# OTEStamper.net
KiCad netlist of a schematic drawn in EAGLE
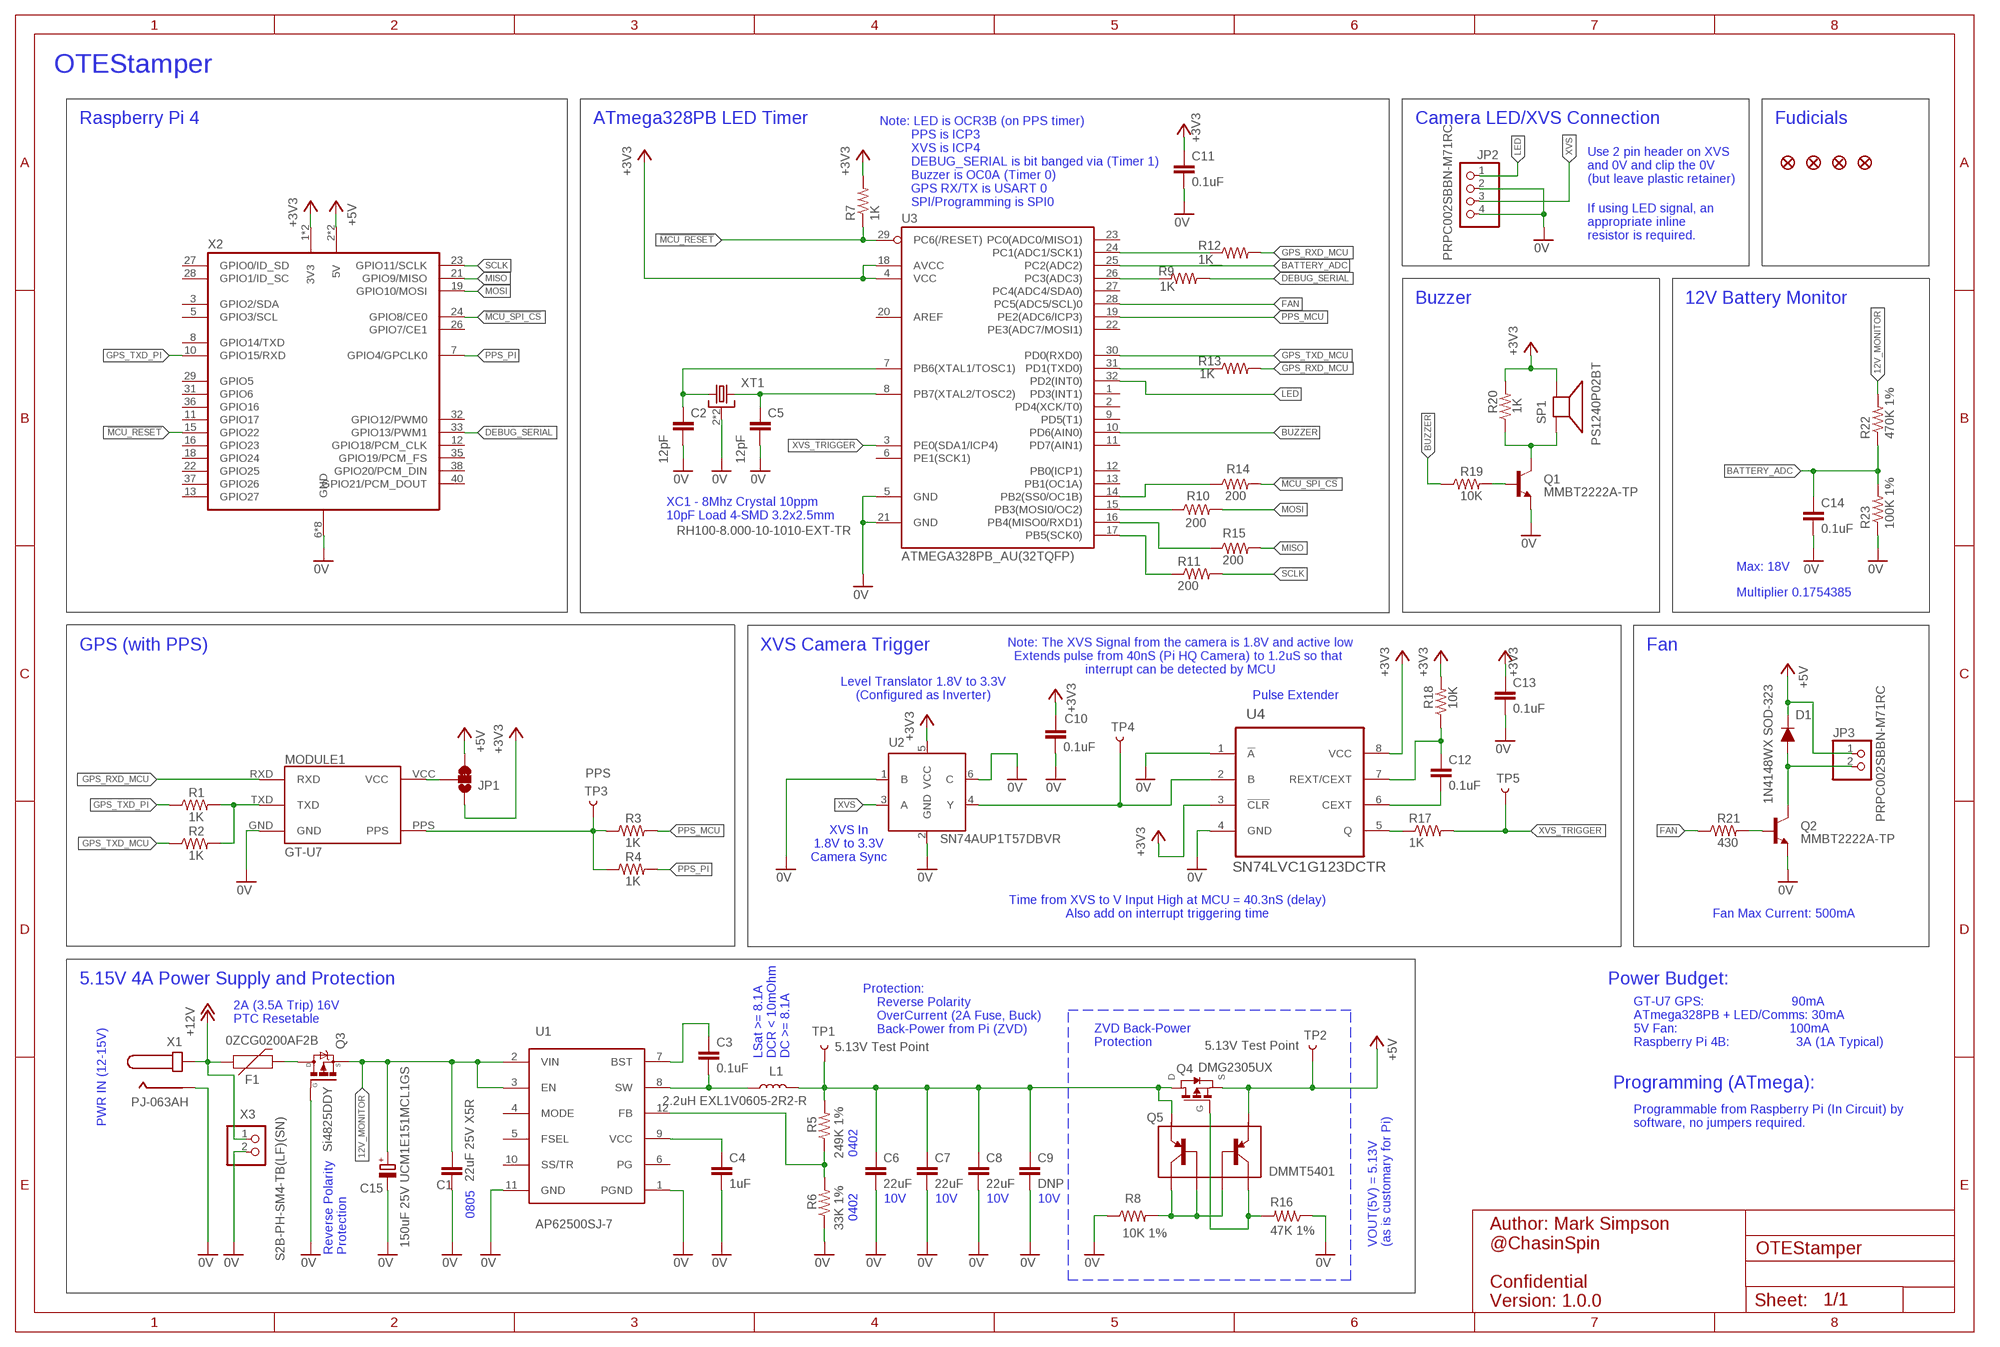
[diagram p0: schematic, sheet 1]

(export (version "E")
  (design (tool "Eeschema 10.0.6"))
  (components
    (comp (ref "C1")
      (value "22uF 25V X5R")
      (footprint "eagle-import:C0805K")
      (libsource (lib "eagle-import") (part "C-EUC0805K"))
    )
    (comp (ref "C2")
      (value "12pF")
      (footprint "eagle-import:C0603K")
      (libsource (lib "eagle-import") (part "C-EU"))
    )
    (comp (ref "C3")
      (value "0.1uF")
      (footprint "eagle-import:C0402K")
      (libsource (lib "eagle-import") (part "C-EUC0402K"))
    )
    (comp (ref "C4")
      (value "1uF")
      (footprint "eagle-import:C0402K")
      (libsource (lib "eagle-import") (part "C-EUC0402K"))
    )
    (comp (ref "C5")
      (value "12pF")
      (footprint "eagle-import:C0603K")
      (libsource (lib "eagle-import") (part "C-EU"))
    )
    (comp (ref "C6")
      (value "22uF")
      (footprint "eagle-import:C0603K")
      (libsource (lib "eagle-import") (part "C-EU"))
    )
    (comp (ref "C7")
      (value "22uF")
      (footprint "eagle-import:C0603K")
      (libsource (lib "eagle-import") (part "C-EU"))
    )
    (comp (ref "C8")
      (value "22uF")
      (footprint "eagle-import:C0603K")
      (libsource (lib "eagle-import") (part "C-EU"))
    )
    (comp (ref "C9")
      (value "DNP")
      (footprint "eagle-import:C0603K")
      (libsource (lib "eagle-import") (part "C-EU"))
    )
    (comp (ref "C10")
      (value "0.1uF")
      (footprint "eagle-import:C0603K")
      (libsource (lib "eagle-import") (part "C-EU"))
    )
    (comp (ref "C11")
      (value "0.1uF")
      (footprint "eagle-import:C0603K")
      (libsource (lib "eagle-import") (part "C-EU"))
    )
    (comp (ref "C12")
      (value "0.1uF")
      (footprint "eagle-import:C0603K")
      (libsource (lib "eagle-import") (part "C-EU"))
    )
    (comp (ref "C13")
      (value "0.1uF")
      (footprint "eagle-import:C0603K")
      (libsource (lib "eagle-import") (part "C-EU"))
    )
    (comp (ref "C14")
      (value "0.1uF")
      (footprint "eagle-import:C0603K")
      (libsource (lib "eagle-import") (part "C-EU"))
    )
    (comp (ref "C15")
      (value "150uF 25V UCM1E151MCL1GS")
      (footprint "eagle-import:UD-6,3X7,7_NICHICON")
      (libsource (lib "eagle-import") (part "CPOL-EUUD-6,3X7,7"))
    )
    (comp (ref "D1")
      (value "1N4148WX SOD-323")
      (footprint "eagle-import:SOD-323")
      (libsource (lib "eagle-import") (part "DIODE"))
    )
    (comp (ref "F1")
      (value "0ZCG0200AF2B")
      (footprint "eagle-import:F1812")
      (libsource (lib "eagle-import") (part "FUSE-PTCF1812"))
    )
    (comp (ref "FD1")
      (value "FIDUCIALUFIDUCIAL")
      (footprint "eagle-import:FIDUCIAL-MICRO")
      (libsource (lib "eagle-import") (part "FIDUCIALUFIDUCIAL"))
    )
    (comp (ref "FD2")
      (value "FIDUCIALUFIDUCIAL")
      (footprint "eagle-import:FIDUCIAL-MICRO")
      (libsource (lib "eagle-import") (part "FIDUCIALUFIDUCIAL"))
    )
    (comp (ref "FD3")
      (value "FIDUCIALUFIDUCIAL")
      (footprint "eagle-import:FIDUCIAL-MICRO")
      (libsource (lib "eagle-import") (part "FIDUCIALUFIDUCIAL"))
    )
    (comp (ref "FD4")
      (value "FIDUCIALUFIDUCIAL")
      (footprint "eagle-import:FIDUCIAL-MICRO")
      (libsource (lib "eagle-import") (part "FIDUCIALUFIDUCIAL"))
    )
    (comp (ref "JP1")
      (value "JUMPER-SMT_3_1-NC_TRACE_SILK")
      (footprint "eagle-import:SMT-JUMPER_3_1-NC_TRACE_SILK")
      (libsource (lib "eagle-import") (part "JUMPER-SMT_3_1-NC_TRACE_SILK"))
    )
    (comp (ref "JP2")
      (value "PRPC002SBBN-M71RC")
      (footprint "eagle-import:1X04")
      (libsource (lib "eagle-import") (part "PINHD-1X4"))
    )
    (comp (ref "JP3")
      (value "PRPC002SBBN-M71RC")
      (footprint "eagle-import:1X02")
      (libsource (lib "eagle-import") (part "PINHD-1X2"))
    )
    (comp (ref "L1")
      (value "2.2uH EXL1V0605-2R2-R")
      (footprint "eagle-import:EXL1V0605")
      (libsource (lib "eagle-import") (part "EXL1V0605"))
    )
    (comp (ref "MODULE1")
      (value "GT-U7")
      (footprint "eagle-import:GT-U7")
      (libsource (lib "eagle-import") (part "GT-U7"))
    )
    (comp (ref "Q1")
      (value "MMBT2222A-TP")
      (footprint "eagle-import:SOT23-BEC")
      (libsource (lib "eagle-import") (part "MMBT3904LT1G"))
    )
    (comp (ref "Q2")
      (value "MMBT2222A-TP")
      (footprint "eagle-import:SOT23-BEC")
      (libsource (lib "eagle-import") (part "MMBT3904LT1G"))
    )
    (comp (ref "Q3")
      (value "Si4825DDY")
      (footprint "eagle-import:SOIC-8-BAR")
      (libsource (lib "eagle-import") (part "SI4825DDY"))
    )
    (comp (ref "Q4")
      (value "DMG2305UX")
      (footprint "eagle-import:SI2323DDS")
      (libsource (lib "eagle-import") (part "SI2323DDS"))
    )
    (comp (ref "Q5")
      (value "DMMT5401")
      (footprint "eagle-import:SOT26(SC74R)")
      (libsource (lib "eagle-import") (part "DMMT5401"))
    )
    (comp (ref "R1")
      (value "1K")
      (footprint "eagle-import:R0603")
      (libsource (lib "eagle-import") (part "R-US"))
    )
    (comp (ref "R2")
      (value "1K")
      (footprint "eagle-import:R0603")
      (libsource (lib "eagle-import") (part "R-US"))
    )
    (comp (ref "R3")
      (value "1K")
      (footprint "eagle-import:R0603")
      (libsource (lib "eagle-import") (part "R-US"))
    )
    (comp (ref "R4")
      (value "1K")
      (footprint "eagle-import:R0603")
      (libsource (lib "eagle-import") (part "R-US"))
    )
    (comp (ref "R5")
      (value "249K 1%")
      (footprint "eagle-import:R0402")
      (libsource (lib "eagle-import") (part "R-USR0402"))
    )
    (comp (ref "R6")
      (value "33K 1%")
      (footprint "eagle-import:R0402")
      (libsource (lib "eagle-import") (part "R-USR0402"))
    )
    (comp (ref "R7")
      (value "1K")
      (footprint "eagle-import:R0603")
      (libsource (lib "eagle-import") (part "R-US"))
    )
    (comp (ref "R8")
      (value "10K 1%")
      (footprint "eagle-import:R0603")
      (libsource (lib "eagle-import") (part "R-US"))
    )
    (comp (ref "R9")
      (value "1K")
      (footprint "eagle-import:R0603")
      (libsource (lib "eagle-import") (part "R-US"))
    )
    (comp (ref "R10")
      (value "200")
      (footprint "eagle-import:R0603")
      (libsource (lib "eagle-import") (part "R-US"))
    )
    (comp (ref "R11")
      (value "200")
      (footprint "eagle-import:R0603")
      (libsource (lib "eagle-import") (part "R-US"))
    )
    (comp (ref "R12")
      (value "1K")
      (footprint "eagle-import:R0603")
      (libsource (lib "eagle-import") (part "R-US"))
    )
    (comp (ref "R13")
      (value "1K")
      (footprint "eagle-import:R0603")
      (libsource (lib "eagle-import") (part "R-US"))
    )
    (comp (ref "R14")
      (value "200")
      (footprint "eagle-import:R0603")
      (libsource (lib "eagle-import") (part "R-US"))
    )
    (comp (ref "R15")
      (value "200")
      (footprint "eagle-import:R0603")
      (libsource (lib "eagle-import") (part "R-US"))
    )
    (comp (ref "R16")
      (value "47K 1%")
      (footprint "eagle-import:R0603")
      (libsource (lib "eagle-import") (part "R-US"))
    )
    (comp (ref "R17")
      (value "1K")
      (footprint "eagle-import:R0603")
      (libsource (lib "eagle-import") (part "R-US"))
    )
    (comp (ref "R18")
      (value "10K")
      (footprint "eagle-import:R0603")
      (libsource (lib "eagle-import") (part "R-US"))
    )
    (comp (ref "R19")
      (value "10K")
      (footprint "eagle-import:R0603")
      (libsource (lib "eagle-import") (part "R-US"))
    )
    (comp (ref "R20")
      (value "1K")
      (footprint "eagle-import:R0603")
      (libsource (lib "eagle-import") (part "R-US"))
    )
    (comp (ref "R21")
      (value "430")
      (footprint "eagle-import:R0603")
      (libsource (lib "eagle-import") (part "R-US"))
    )
    (comp (ref "R22")
      (value "470K 1%")
      (footprint "eagle-import:R0603")
      (libsource (lib "eagle-import") (part "R-US"))
    )
    (comp (ref "R23")
      (value "100K 1%")
      (footprint "eagle-import:R0603")
      (libsource (lib "eagle-import") (part "R-US"))
    )
    (comp (ref "SP1")
      (value "PS1240P02BT")
      (footprint "eagle-import:PS12")
      (libsource (lib "eagle-import") (part "PS12/PS12"))
    )
    (comp (ref "TP1")
      (value "5.13V Test Point")
      (footprint "eagle-import:PAD.03X.03")
      (libsource (lib "eagle-import") (part "TEST-POINT3"))
    )
    (comp (ref "TP2")
      (value "5.13V Test Point")
      (footprint "eagle-import:PAD.03X.03")
      (libsource (lib "eagle-import") (part "TEST-POINT3"))
    )
    (comp (ref "TP3")
      (value "PPS")
      (footprint "eagle-import:PAD.03X.03")
      (libsource (lib "eagle-import") (part "TEST-POINT3"))
    )
    (comp (ref "TP4")
      (value "TEST-POINT3")
      (footprint "eagle-import:PAD.03X.03")
      (libsource (lib "eagle-import") (part "TEST-POINT3"))
    )
    (comp (ref "TP5")
      (value "TEST-POINT3")
      (footprint "eagle-import:PAD.03X.03")
      (libsource (lib "eagle-import") (part "TEST-POINT3"))
    )
    (comp (ref "U1")
      (value "AP62500SJ-7")
      (footprint "eagle-import:AP62500")
      (libsource (lib "eagle-import") (part "AP62500"))
    )
    (comp (ref "U2")
      (value "SN74AUP1T57DBVR")
      (footprint "eagle-import:SOT23-6-DBV")
      (libsource (lib "eagle-import") (part "SN74AUP1T57"))
    )
    (comp (ref "U3")
      (value "ATMEGA328PB_AU(32TQFP)")
      (footprint "eagle-import:TQFP32-08")
      (libsource (lib "eagle-import") (part "ATMEGA328PB_TQFP"))
    )
    (comp (ref "U4")
      (value "SN74LVC1G123DCTR")
      (footprint "eagle-import:SSOP-8-DCT")
      (libsource (lib "eagle-import") (part "SN74LVC1G123DCT"))
    )
    (comp (ref "X1")
      (value "PJ-063AH")
      (footprint "eagle-import:PJ-063AH")
      (libsource (lib "eagle-import") (part "PJ-063AH"))
    )
    (comp (ref "X2")
      (value "ADAFRUIT_2222")
      (footprint "eagle-import:RASPBERRY_PI_HAT")
      (libsource (lib "eagle-import") (part "RASPBERRY_PI_HAT"))
    )
    (comp (ref "X3")
      (value "S2B-PH-SM4-TB(LF)(SN)")
      (footprint "eagle-import:JST-PH-2-SMT-RA")
      (libsource (lib "eagle-import") (part "S2B-PH-SM4-TB(LF)(SN)"))
    )
    (comp (ref "XT1")
      (value "RH100-8.000-10-1010-EXT-TR")
      (footprint "eagle-import:ECS-ECX-32")
      (libsource (lib "eagle-import") (part "ECS-ECX-32"))
    )
  )
  (nets
    (net (code "1") (name "+3V3") (class "Default")
      (node (ref "C10") (pin "1") (pinfunction "1_1") (pintype "passive"))
      (node (ref "C11") (pin "1") (pinfunction "1_1") (pintype "passive"))
      (node (ref "C13") (pin "1") (pinfunction "1_1") (pintype "passive"))
      (node (ref "JP1") (pin "1") (pinfunction "1_1") (pintype "passive"))
      (node (ref "R18") (pin "2") (pinfunction "2_2") (pintype "passive"))
      (node (ref "R20") (pin "2") (pinfunction "2_2") (pintype "passive"))
      (node (ref "R7") (pin "2") (pinfunction "2_2") (pintype "passive"))
      (node (ref "SP1") (pin "P$1") (pinfunction "+_P$1") (pintype "passive"))
      (node (ref "U2") (pin "5") (pinfunction "VCC_5") (pintype "power_in"))
      (node (ref "U3") (pin "18") (pinfunction "AVCC_18") (pintype "bidirectional"))
      (node (ref "U3") (pin "4") (pinfunction "VCC_4") (pintype "bidirectional"))
      (node (ref "U4") (pin "3") (pinfunction "~{CLR}_3") (pintype "input"))
      (node (ref "U4") (pin "8") (pinfunction "VCC_8") (pintype "power_in"))
      (node (ref "X2") (pin "1") (pinfunction "3V3_1") (pintype "bidirectional"))
      (node (ref "X2") (pin "17") (pinfunction "3V3_17") (pintype "bidirectional"))
    )
    (net (code "2") (name "+5V") (class "Default")
      (node (ref "D1") (pin "CATHODE") (pinfunction "K_CATHODE") (pintype "passive"))
      (node (ref "JP1") (pin "3") (pinfunction "3_3") (pintype "passive"))
      (node (ref "JP3") (pin "1") (pinfunction "1_1") (pintype "passive"))
      (node (ref "Q4") (pin "2") (pinfunction "S_2") (pintype "passive"))
      (node (ref "Q5") (pin "5") (pinfunction "E2_5") (pintype "passive"))
      (node (ref "TP2") (pin "P$1") (pinfunction "1_P$1") (pintype "bidirectional"))
      (node (ref "X2") (pin "2") (pinfunction "5V_2") (pintype "bidirectional"))
      (node (ref "X2") (pin "4") (pinfunction "5V_4") (pintype "bidirectional"))
    )
    (net (code "3") (name "+12V") (class "Default")
      (node (ref "F1") (pin "1") (pinfunction "1_1") (pintype "bidirectional"))
      (node (ref "X1") (pin "1") (pinfunction "POS_1") (pintype "passive"))
      (node (ref "X3") (pin "1") (pinfunction "1_1") (pintype "passive"))
    )
    (net (code "4") (name "/~{MCU_RESET}") (class "Default")
      (node (ref "R7") (pin "1") (pinfunction "1_1") (pintype "passive"))
      (node (ref "U3") (pin "29") (pinfunction "PC6(/RESET)_29") (pintype "bidirectional"))
      (node (ref "X2") (pin "15") (pinfunction "GPIO22_15") (pintype "bidirectional"))
    )
    (net (code "5") (name "/~{MCU_SPI_CS}") (class "Default")
      (node (ref "R14") (pin "2") (pinfunction "2_2") (pintype "passive"))
      (node (ref "X2") (pin "24") (pinfunction "GPIO8/CE0_24") (pintype "bidirectional"))
    )
    (net (code "6") (name "0V") (class "Default")
      (node (ref "C1") (pin "2") (pinfunction "2_2") (pintype "passive"))
      (node (ref "C10") (pin "2") (pinfunction "2_2") (pintype "passive"))
      (node (ref "C11") (pin "2") (pinfunction "2_2") (pintype "passive"))
      (node (ref "C13") (pin "2") (pinfunction "2_2") (pintype "passive"))
      (node (ref "C14") (pin "2") (pinfunction "2_2") (pintype "passive"))
      (node (ref "C15") (pin "-") (pinfunction "-_-") (pintype "passive"))
      (node (ref "C2") (pin "2") (pinfunction "2_2") (pintype "passive"))
      (node (ref "C4") (pin "2") (pinfunction "2_2") (pintype "passive"))
      (node (ref "C5") (pin "2") (pinfunction "2_2") (pintype "passive"))
      (node (ref "C6") (pin "2") (pinfunction "2_2") (pintype "passive"))
      (node (ref "C7") (pin "2") (pinfunction "2_2") (pintype "passive"))
      (node (ref "C8") (pin "2") (pinfunction "2_2") (pintype "passive"))
      (node (ref "C9") (pin "2") (pinfunction "2_2") (pintype "passive"))
      (node (ref "JP2") (pin "2") (pinfunction "2_2") (pintype "passive"))
      (node (ref "JP2") (pin "4") (pinfunction "4_4") (pintype "passive"))
      (node (ref "MODULE1") (pin "GND") (pinfunction "GND_GND") (pintype "power_in"))
      (node (ref "Q1") (pin "E") (pinfunction "E_E") (pintype "passive"))
      (node (ref "Q2") (pin "E") (pinfunction "E_E") (pintype "passive"))
      (node (ref "Q3") (pin "4") (pinfunction "G_4") (pintype "passive"))
      (node (ref "R16") (pin "1") (pinfunction "1_1") (pintype "passive"))
      (node (ref "R23") (pin "1") (pinfunction "1_1") (pintype "passive"))
      (node (ref "R6") (pin "1") (pinfunction "1_1") (pintype "passive"))
      (node (ref "R8") (pin "1") (pinfunction "1_1") (pintype "passive"))
      (node (ref "U1") (pin "1") (pinfunction "PGND_1") (pintype "power_in"))
      (node (ref "U1") (pin "11") (pinfunction "GND_11") (pintype "power_in"))
      (node (ref "U2") (pin "1") (pinfunction "B_1") (pintype "input"))
      (node (ref "U2") (pin "2") (pinfunction "GND_2") (pintype "power_in"))
      (node (ref "U2") (pin "6") (pinfunction "C_6") (pintype "input"))
      (node (ref "U3") (pin "21") (pinfunction "GND_21") (pintype "bidirectional"))
      (node (ref "U3") (pin "5") (pinfunction "GND_5") (pintype "bidirectional"))
      (node (ref "U4") (pin "1") (pinfunction "~{A}_1") (pintype "input"))
      (node (ref "U4") (pin "4") (pinfunction "GND_4") (pintype "power_in"))
      (node (ref "X1") (pin "2") (pinfunction "NEG_2") (pintype "passive"))
      (node (ref "X1") (pin "SHIELD1") (pinfunction "NEG_SHIELD1") (pintype "passive"))
      (node (ref "X1") (pin "SHIELD2") (pinfunction "NEG_SHIELD2") (pintype "passive"))
      (node (ref "X2") (pin "14") (pinfunction "GND_14") (pintype "bidirectional"))
      (node (ref "X2") (pin "20") (pinfunction "GND_20") (pintype "bidirectional"))
      (node (ref "X2") (pin "25") (pinfunction "GND_25") (pintype "bidirectional"))
      (node (ref "X2") (pin "30") (pinfunction "GND_30") (pintype "bidirectional"))
      (node (ref "X2") (pin "34") (pinfunction "GND_34") (pintype "bidirectional"))
      (node (ref "X2") (pin "39") (pinfunction "GND_39") (pintype "bidirectional"))
      (node (ref "X2") (pin "6") (pinfunction "GND_6") (pintype "bidirectional"))
      (node (ref "X2") (pin "9") (pinfunction "GND_9") (pintype "bidirectional"))
      (node (ref "X3") (pin "2") (pinfunction "2_2") (pintype "passive"))
      (node (ref "XT1") (pin "2") (pinfunction "3_2") (pintype "power_in"))
      (node (ref "XT1") (pin "4") (pinfunction "3_4") (pintype "power_in"))
    )
    (net (code "7") (name "12V_MONITOR") (class "Default")
      (node (ref "C1") (pin "1") (pinfunction "1_1") (pintype "passive"))
      (node (ref "C15") (pin "+") (pinfunction "+_+") (pintype "passive"))
      (node (ref "Q3") (pin "1") (pinfunction "S_1") (pintype "passive"))
      (node (ref "Q3") (pin "2") (pinfunction "S_2") (pintype "passive"))
      (node (ref "Q3") (pin "3") (pinfunction "S_3") (pintype "passive"))
      (node (ref "R22") (pin "2") (pinfunction "2_2") (pintype "passive"))
      (node (ref "U1") (pin "2") (pinfunction "VIN_2") (pintype "power_in"))
      (node (ref "U1") (pin "3") (pinfunction "EN_3") (pintype "input"))
    )
    (net (code "8") (name "BATTERY_ADC") (class "Default")
      (node (ref "C14") (pin "1") (pinfunction "1_1") (pintype "passive"))
      (node (ref "R22") (pin "1") (pinfunction "1_1") (pintype "passive"))
      (node (ref "R23") (pin "2") (pinfunction "2_2") (pintype "passive"))
      (node (ref "U3") (pin "25") (pinfunction "PC2(ADC2)_25") (pintype "bidirectional"))
    )
    (net (code "9") (name "BUZZER") (class "Default")
      (node (ref "R19") (pin "1") (pinfunction "1_1") (pintype "passive"))
      (node (ref "U3") (pin "10") (pinfunction "PD6(AIN0)_10") (pintype "bidirectional"))
    )
    (net (code "10") (name "DEBUG_SERIAL") (class "Default")
      (node (ref "R9") (pin "2") (pinfunction "2_2") (pintype "passive"))
      (node (ref "X2") (pin "33") (pinfunction "GPIO13/PWM1_33") (pintype "bidirectional"))
    )
    (net (code "11") (name "FAN") (class "Default")
      (node (ref "R21") (pin "1") (pinfunction "1_1") (pintype "passive"))
      (node (ref "U3") (pin "28") (pinfunction "PC5(ADC5/SCL)0_28") (pintype "bidirectional"))
    )
    (net (code "12") (name "GPS_RXD_MCU") (class "Default")
      (node (ref "MODULE1") (pin "RXD") (pinfunction "RXD_RXD") (pintype "input"))
      (node (ref "R12") (pin "2") (pinfunction "2_2") (pintype "passive"))
      (node (ref "R13") (pin "2") (pinfunction "2_2") (pintype "passive"))
    )
    (net (code "13") (name "GPS_TXD_MCU") (class "Default")
      (node (ref "R2") (pin "1") (pinfunction "1_1") (pintype "passive"))
      (node (ref "U3") (pin "30") (pinfunction "PD0(RXD0)_30") (pintype "bidirectional"))
    )
    (net (code "14") (name "GPS_TXD_PI") (class "Default")
      (node (ref "R1") (pin "1") (pinfunction "1_1") (pintype "passive"))
      (node (ref "X2") (pin "10") (pinfunction "GPIO15/RXD_10") (pintype "bidirectional"))
    )
    (net (code "15") (name "LED") (class "Default")
      (node (ref "JP2") (pin "1") (pinfunction "1_1") (pintype "passive"))
      (node (ref "U3") (pin "32") (pinfunction "PD2(INT0)_32") (pintype "bidirectional"))
    )
    (net (code "16") (name "MISO") (class "Default")
      (node (ref "R15") (pin "2") (pinfunction "2_2") (pintype "passive"))
      (node (ref "X2") (pin "21") (pinfunction "GPIO9/MISO_21") (pintype "bidirectional"))
    )
    (net (code "17") (name "MOSI") (class "Default")
      (node (ref "R10") (pin "2") (pinfunction "2_2") (pintype "passive"))
      (node (ref "X2") (pin "19") (pinfunction "GPIO10/MOSI_19") (pintype "bidirectional"))
    )
    (net (code "18") (name "Net-(D1-A)") (class "Default")
      (node (ref "D1") (pin "ANODE") (pinfunction "A_ANODE") (pintype "passive"))
      (node (ref "JP3") (pin "2") (pinfunction "2_2") (pintype "passive"))
      (node (ref "Q2") (pin "C") (pinfunction "C_C") (pintype "passive"))
    )
    (net (code "19") (name "Net-(F1-Pad2)") (class "Default")
      (node (ref "F1") (pin "2") (pinfunction "2_2") (pintype "bidirectional"))
      (node (ref "Q3") (pin "5") (pinfunction "D_5") (pintype "passive"))
      (node (ref "Q3") (pin "6") (pinfunction "D_6") (pintype "passive"))
      (node (ref "Q3") (pin "7") (pinfunction "D_7") (pintype "passive"))
      (node (ref "Q3") (pin "8") (pinfunction "D_8") (pintype "passive"))
    )
    (net (code "20") (name "Net-(JP1-Pad2)") (class "Default")
      (node (ref "JP1") (pin "2") (pinfunction "2_2") (pintype "passive"))
      (node (ref "MODULE1") (pin "VCC") (pinfunction "VCC_VCC") (pintype "power_in"))
    )
    (net (code "21") (name "Net-(MODULE1-PadTXD)") (class "Default")
      (node (ref "MODULE1") (pin "TXD") (pinfunction "TXD_TXD") (pintype "output"))
      (node (ref "R1") (pin "2") (pinfunction "2_2") (pintype "passive"))
      (node (ref "R2") (pin "2") (pinfunction "2_2") (pintype "passive"))
    )
    (net (code "22") (name "Net-(Q1-PadB)") (class "Default")
      (node (ref "Q1") (pin "B") (pinfunction "B_B") (pintype "passive"))
      (node (ref "R19") (pin "2") (pinfunction "2_2") (pintype "passive"))
    )
    (net (code "23") (name "Net-(Q2-PadB)") (class "Default")
      (node (ref "Q2") (pin "B") (pinfunction "B_B") (pintype "passive"))
      (node (ref "R21") (pin "2") (pinfunction "2_2") (pintype "passive"))
    )
    (net (code "24") (name "Net-(Q4-D)") (class "Default")
      (node (ref "C6") (pin "1") (pinfunction "1_1") (pintype "passive"))
      (node (ref "C7") (pin "1") (pinfunction "1_1") (pintype "passive"))
      (node (ref "C8") (pin "1") (pinfunction "1_1") (pintype "passive"))
      (node (ref "C9") (pin "1") (pinfunction "1_1") (pintype "passive"))
      (node (ref "L1") (pin "2") (pinfunction "2_2") (pintype "passive"))
      (node (ref "Q4") (pin "3") (pinfunction "D_3") (pintype "passive"))
      (node (ref "Q5") (pin "6") (pinfunction "E1_6") (pintype "passive"))
      (node (ref "R5") (pin "2") (pinfunction "2_2") (pintype "passive"))
      (node (ref "TP1") (pin "P$1") (pinfunction "1_P$1") (pintype "bidirectional"))
    )
    (net (code "25") (name "Net-(Q4-G)") (class "Default")
      (node (ref "Q4") (pin "1") (pinfunction "G_1") (pintype "passive"))
      (node (ref "Q5") (pin "4") (pinfunction "C2_4") (pintype "passive"))
      (node (ref "R16") (pin "2") (pinfunction "2_2") (pintype "passive"))
    )
    (net (code "26") (name "Net-(Q5-B1)") (class "Default")
      (node (ref "Q5") (pin "1") (pinfunction "C1_1") (pintype "passive"))
      (node (ref "Q5") (pin "2") (pinfunction "B1_2") (pintype "passive"))
      (node (ref "Q5") (pin "3") (pinfunction "B2_3") (pintype "passive"))
      (node (ref "R8") (pin "2") (pinfunction "2_2") (pintype "passive"))
    )
    (net (code "27") (name "Net-(SP1--)") (class "Default")
      (node (ref "Q1") (pin "C") (pinfunction "C_C") (pintype "passive"))
      (node (ref "R20") (pin "1") (pinfunction "1_1") (pintype "passive"))
      (node (ref "SP1") (pin "P$2") (pinfunction "-_P$2") (pintype "passive"))
    )
    (net (code "28") (name "Net-(TP3-1)") (class "Default")
      (node (ref "MODULE1") (pin "PPS") (pinfunction "PPS_PPS") (pintype "output"))
      (node (ref "R3") (pin "1") (pinfunction "1_1") (pintype "passive"))
      (node (ref "R4") (pin "1") (pinfunction "1_1") (pintype "passive"))
      (node (ref "TP3") (pin "P$1") (pinfunction "1_P$1") (pintype "bidirectional"))
    )
    (net (code "29") (name "Net-(TP4-1)") (class "Default")
      (node (ref "TP4") (pin "P$1") (pinfunction "1_P$1") (pintype "bidirectional"))
      (node (ref "U2") (pin "4") (pinfunction "Y_4") (pintype "output"))
      (node (ref "U4") (pin "2") (pinfunction "B_2") (pintype "input"))
    )
    (net (code "30") (name "Net-(U1-BST)") (class "Default")
      (node (ref "C3") (pin "1") (pinfunction "1_1") (pintype "passive"))
      (node (ref "U1") (pin "7") (pinfunction "BST_7") (pintype "input"))
    )
    (net (code "31") (name "Net-(U1-FB)") (class "Default")
      (node (ref "R5") (pin "1") (pinfunction "1_1") (pintype "passive"))
      (node (ref "R6") (pin "2") (pinfunction "2_2") (pintype "passive"))
      (node (ref "U1") (pin "12") (pinfunction "FB_12") (pintype "input"))
    )
    (net (code "32") (name "Net-(U1-SW)") (class "Default")
      (node (ref "C3") (pin "2") (pinfunction "2_2") (pintype "passive"))
      (node (ref "L1") (pin "1") (pinfunction "1_1") (pintype "passive"))
      (node (ref "U1") (pin "8") (pinfunction "SW_8") (pintype "power_in"))
    )
    (net (code "33") (name "Net-(U1-VCC)") (class "Default")
      (node (ref "C4") (pin "1") (pinfunction "1_1") (pintype "passive"))
      (node (ref "U1") (pin "9") (pinfunction "VCC_9") (pintype "power_in"))
    )
    (net (code "34") (name "Net-(U3-PB2(SS0{slash}OC1B))") (class "Default")
      (node (ref "R14") (pin "1") (pinfunction "1_1") (pintype "passive"))
      (node (ref "U3") (pin "14") (pinfunction "PB2(SS0/OC1B)_14") (pintype "bidirectional"))
    )
    (net (code "35") (name "Net-(U3-PB3(MOSI0{slash}OC2))") (class "Default")
      (node (ref "R10") (pin "1") (pinfunction "1_1") (pintype "passive"))
      (node (ref "U3") (pin "15") (pinfunction "PB3(MOSI0/OC2)_15") (pintype "bidirectional"))
    )
    (net (code "36") (name "Net-(U3-PB4(MISO0{slash}RXD1))") (class "Default")
      (node (ref "R15") (pin "1") (pinfunction "1_1") (pintype "passive"))
      (node (ref "U3") (pin "16") (pinfunction "PB4(MISO0/RXD1)_16") (pintype "bidirectional"))
    )
    (net (code "37") (name "Net-(U3-PB5(SCK0))") (class "Default")
      (node (ref "R11") (pin "1") (pinfunction "1_1") (pintype "passive"))
      (node (ref "U3") (pin "17") (pinfunction "PB5(SCK0)_17") (pintype "bidirectional"))
    )
    (net (code "38") (name "Net-(U3-PB6(XTAL1{slash}TOSC1))") (class "Default")
      (node (ref "C2") (pin "1") (pinfunction "1_1") (pintype "passive"))
      (node (ref "U3") (pin "7") (pinfunction "PB6(XTAL1/TOSC1)_7") (pintype "bidirectional"))
      (node (ref "XT1") (pin "1") (pinfunction "1_1") (pintype "passive"))
    )
    (net (code "39") (name "Net-(U3-PB7(XTAL2{slash}TOSC2))") (class "Default")
      (node (ref "C5") (pin "1") (pinfunction "1_1") (pintype "passive"))
      (node (ref "U3") (pin "8") (pinfunction "PB7(XTAL2/TOSC2)_8") (pintype "bidirectional"))
      (node (ref "XT1") (pin "3") (pinfunction "2_3") (pintype "passive"))
    )
    (net (code "40") (name "Net-(U3-PC1(ADC1{slash}SCK1))") (class "Default")
      (node (ref "R12") (pin "1") (pinfunction "1_1") (pintype "passive"))
      (node (ref "U3") (pin "24") (pinfunction "PC1(ADC1/SCK1)_24") (pintype "bidirectional"))
    )
    (net (code "41") (name "Net-(U3-PC3(ADC3))") (class "Default")
      (node (ref "R9") (pin "1") (pinfunction "1_1") (pintype "passive"))
      (node (ref "U3") (pin "26") (pinfunction "PC3(ADC3)_26") (pintype "bidirectional"))
    )
    (net (code "42") (name "Net-(U3-PD1(TXD0))") (class "Default")
      (node (ref "R13") (pin "1") (pinfunction "1_1") (pintype "passive"))
      (node (ref "U3") (pin "31") (pinfunction "PD1(TXD0)_31") (pintype "bidirectional"))
    )
    (net (code "43") (name "Net-(U4-CEXT)") (class "Default")
      (node (ref "C12") (pin "2") (pinfunction "2_2") (pintype "passive"))
      (node (ref "U4") (pin "6") (pinfunction "CEXT_6") (pintype "passive"))
    )
    (net (code "44") (name "Net-(U4-Q)") (class "Default")
      (node (ref "R17") (pin "1") (pinfunction "1_1") (pintype "passive"))
      (node (ref "U4") (pin "5") (pinfunction "Q_5") (pintype "output"))
    )
    (net (code "45") (name "Net-(U4-REXT{slash}CEXT)") (class "Default")
      (node (ref "C12") (pin "1") (pinfunction "1_1") (pintype "passive"))
      (node (ref "R18") (pin "1") (pinfunction "1_1") (pintype "passive"))
      (node (ref "U4") (pin "7") (pinfunction "REXT/CEXT_7") (pintype "passive"))
    )
    (net (code "46") (name "PPS_MCU") (class "Default")
      (node (ref "R3") (pin "2") (pinfunction "2_2") (pintype "passive"))
      (node (ref "U3") (pin "19") (pinfunction "PE2(ADC6/ICP3)_19") (pintype "bidirectional"))
    )
    (net (code "47") (name "PPS_PI") (class "Default")
      (node (ref "R4") (pin "2") (pinfunction "2_2") (pintype "passive"))
      (node (ref "X2") (pin "7") (pinfunction "GPIO4/GPCLK0_7") (pintype "bidirectional"))
    )
    (net (code "48") (name "SCLK") (class "Default")
      (node (ref "R11") (pin "2") (pinfunction "2_2") (pintype "passive"))
      (node (ref "X2") (pin "23") (pinfunction "GPIO11/SCLK_23") (pintype "bidirectional"))
    )
    (net (code "49") (name "XVS") (class "Default")
      (node (ref "JP2") (pin "3") (pinfunction "3_3") (pintype "passive"))
      (node (ref "U2") (pin "3") (pinfunction "A_3") (pintype "input"))
    )
    (net (code "50") (name "XVS_TRIGGER") (class "Default")
      (node (ref "R17") (pin "2") (pinfunction "2_2") (pintype "passive"))
      (node (ref "TP5") (pin "P$1") (pinfunction "1_P$1") (pintype "bidirectional"))
      (node (ref "U3") (pin "3") (pinfunction "PE0(SDA1/ICP4)_3") (pintype "bidirectional"))
    )
    (net (code "51") (name "unconnected-(U1-FSEL-Pad5)") (class "Default")
      (node (ref "U1") (pin "5") (pinfunction "FSEL_5") (pintype "input"))
    )
    (net (code "52") (name "unconnected-(U1-MODE-Pad4)") (class "Default")
      (node (ref "U1") (pin "4") (pinfunction "MODE_4") (pintype "input"))
    )
    (net (code "53") (name "unconnected-(U1-PG-Pad6)") (class "Default")
      (node (ref "U1") (pin "6") (pinfunction "PG_6") (pintype "output"))
    )
    (net (code "54") (name "unconnected-(U1-SS{slash}TR-Pad10)") (class "Default")
      (node (ref "U1") (pin "10") (pinfunction "SS/TR_10") (pintype "input"))
    )
    (net (code "55") (name "unconnected-(U3-AREF-Pad20)") (class "Default")
      (node (ref "U3") (pin "20") (pinfunction "AREF_20") (pintype "bidirectional"))
    )
    (net (code "56") (name "unconnected-(U3-PB0(ICP1)-Pad12)") (class "Default")
      (node (ref "U3") (pin "12") (pinfunction "PB0(ICP1)_12") (pintype "bidirectional"))
    )
    (net (code "57") (name "unconnected-(U3-PB1(OC1A)-Pad13)") (class "Default")
      (node (ref "U3") (pin "13") (pinfunction "PB1(OC1A)_13") (pintype "bidirectional"))
    )
    (net (code "58") (name "unconnected-(U3-PC0(ADC0{slash}MISO1)-Pad23)") (class "Default")
      (node (ref "U3") (pin "23") (pinfunction "PC0(ADC0/MISO1)_23") (pintype "bidirectional"))
    )
    (net (code "59") (name "unconnected-(U3-PC4(ADC4{slash}SDA0)-Pad27)") (class "Default")
      (node (ref "U3") (pin "27") (pinfunction "PC4(ADC4/SDA0)_27") (pintype "bidirectional"))
    )
    (net (code "60") (name "unconnected-(U3-PD3(INT1)-Pad1)") (class "Default")
      (node (ref "U3") (pin "1") (pinfunction "PD3(INT1)_1") (pintype "bidirectional"))
    )
    (net (code "61") (name "unconnected-(U3-PD4(XCK{slash}T0)-Pad2)") (class "Default")
      (node (ref "U3") (pin "2") (pinfunction "PD4(XCK/T0)_2") (pintype "bidirectional"))
    )
    (net (code "62") (name "unconnected-(U3-PD5(T1)-Pad9)") (class "Default")
      (node (ref "U3") (pin "9") (pinfunction "PD5(T1)_9") (pintype "bidirectional"))
    )
    (net (code "63") (name "unconnected-(U3-PD7(AIN1)-Pad11)") (class "Default")
      (node (ref "U3") (pin "11") (pinfunction "PD7(AIN1)_11") (pintype "bidirectional"))
    )
    (net (code "64") (name "unconnected-(U3-PE1(SCK1)-Pad6)") (class "Default")
      (node (ref "U3") (pin "6") (pinfunction "PE1(SCK1)_6") (pintype "bidirectional"))
    )
    (net (code "65") (name "unconnected-(U3-PE3(ADC7{slash}MOSI1)-Pad22)") (class "Default")
      (node (ref "U3") (pin "22") (pinfunction "PE3(ADC7/MOSI1)_22") (pintype "bidirectional"))
    )
    (net (code "66") (name "unconnected-(X2-GPIO0{slash}ID_SD-Pad27)") (class "Default")
      (node (ref "X2") (pin "27") (pinfunction "GPIO0/ID_SD_27") (pintype "bidirectional"))
    )
    (net (code "67") (name "unconnected-(X2-GPIO1{slash}ID_SC-Pad28)") (class "Default")
      (node (ref "X2") (pin "28") (pinfunction "GPIO1/ID_SC_28") (pintype "bidirectional"))
    )
    (net (code "68") (name "unconnected-(X2-GPIO2{slash}SDA-Pad3)") (class "Default")
      (node (ref "X2") (pin "3") (pinfunction "GPIO2/SDA_3") (pintype "bidirectional"))
    )
    (net (code "69") (name "unconnected-(X2-GPIO3{slash}SCL-Pad5)") (class "Default")
      (node (ref "X2") (pin "5") (pinfunction "GPIO3/SCL_5") (pintype "bidirectional"))
    )
    (net (code "70") (name "unconnected-(X2-GPIO5-Pad29)") (class "Default")
      (node (ref "X2") (pin "29") (pinfunction "GPIO5_29") (pintype "bidirectional"))
    )
    (net (code "71") (name "unconnected-(X2-GPIO6-Pad31)") (class "Default")
      (node (ref "X2") (pin "31") (pinfunction "GPIO6_31") (pintype "bidirectional"))
    )
    (net (code "72") (name "unconnected-(X2-GPIO7{slash}CE1-Pad26)") (class "Default")
      (node (ref "X2") (pin "26") (pinfunction "GPIO7/CE1_26") (pintype "bidirectional"))
    )
    (net (code "73") (name "unconnected-(X2-GPIO12{slash}PWM0-Pad32)") (class "Default")
      (node (ref "X2") (pin "32") (pinfunction "GPIO12/PWM0_32") (pintype "bidirectional"))
    )
    (net (code "74") (name "unconnected-(X2-GPIO14{slash}TXD-Pad8)") (class "Default")
      (node (ref "X2") (pin "8") (pinfunction "GPIO14/TXD_8") (pintype "bidirectional"))
    )
    (net (code "75") (name "unconnected-(X2-GPIO16-Pad36)") (class "Default")
      (node (ref "X2") (pin "36") (pinfunction "GPIO16_36") (pintype "bidirectional"))
    )
    (net (code "76") (name "unconnected-(X2-GPIO17-Pad11)") (class "Default")
      (node (ref "X2") (pin "11") (pinfunction "GPIO17_11") (pintype "bidirectional"))
    )
    (net (code "77") (name "unconnected-(X2-GPIO18{slash}PCM_CLK-Pad12)") (class "Default")
      (node (ref "X2") (pin "12") (pinfunction "GPIO18/PCM_CLK_12") (pintype "bidirectional"))
    )
    (net (code "78") (name "unconnected-(X2-GPIO19{slash}PCM_FS-Pad35)") (class "Default")
      (node (ref "X2") (pin "35") (pinfunction "GPIO19/PCM_FS_35") (pintype "bidirectional"))
    )
    (net (code "79") (name "unconnected-(X2-GPIO20{slash}PCM_DIN-Pad38)") (class "Default")
      (node (ref "X2") (pin "38") (pinfunction "GPIO20/PCM_DIN_38") (pintype "bidirectional"))
    )
    (net (code "80") (name "unconnected-(X2-GPIO21{slash}PCM_DOUT-Pad40)") (class "Default")
      (node (ref "X2") (pin "40") (pinfunction "GPIO21/PCM_DOUT_40") (pintype "bidirectional"))
    )
    (net (code "81") (name "unconnected-(X2-GPIO23-Pad16)") (class "Default")
      (node (ref "X2") (pin "16") (pinfunction "GPIO23_16") (pintype "bidirectional"))
    )
    (net (code "82") (name "unconnected-(X2-GPIO24-Pad18)") (class "Default")
      (node (ref "X2") (pin "18") (pinfunction "GPIO24_18") (pintype "bidirectional"))
    )
    (net (code "83") (name "unconnected-(X2-GPIO25-Pad22)") (class "Default")
      (node (ref "X2") (pin "22") (pinfunction "GPIO25_22") (pintype "bidirectional"))
    )
    (net (code "84") (name "unconnected-(X2-GPIO26-Pad37)") (class "Default")
      (node (ref "X2") (pin "37") (pinfunction "GPIO26_37") (pintype "bidirectional"))
    )
    (net (code "85") (name "unconnected-(X2-GPIO27-Pad13)") (class "Default")
      (node (ref "X2") (pin "13") (pinfunction "GPIO27_13") (pintype "bidirectional"))
    )
  )
)
